# Acoustics_Preamp.net
KiCad netlist of a schematic drawn in Altium Designer
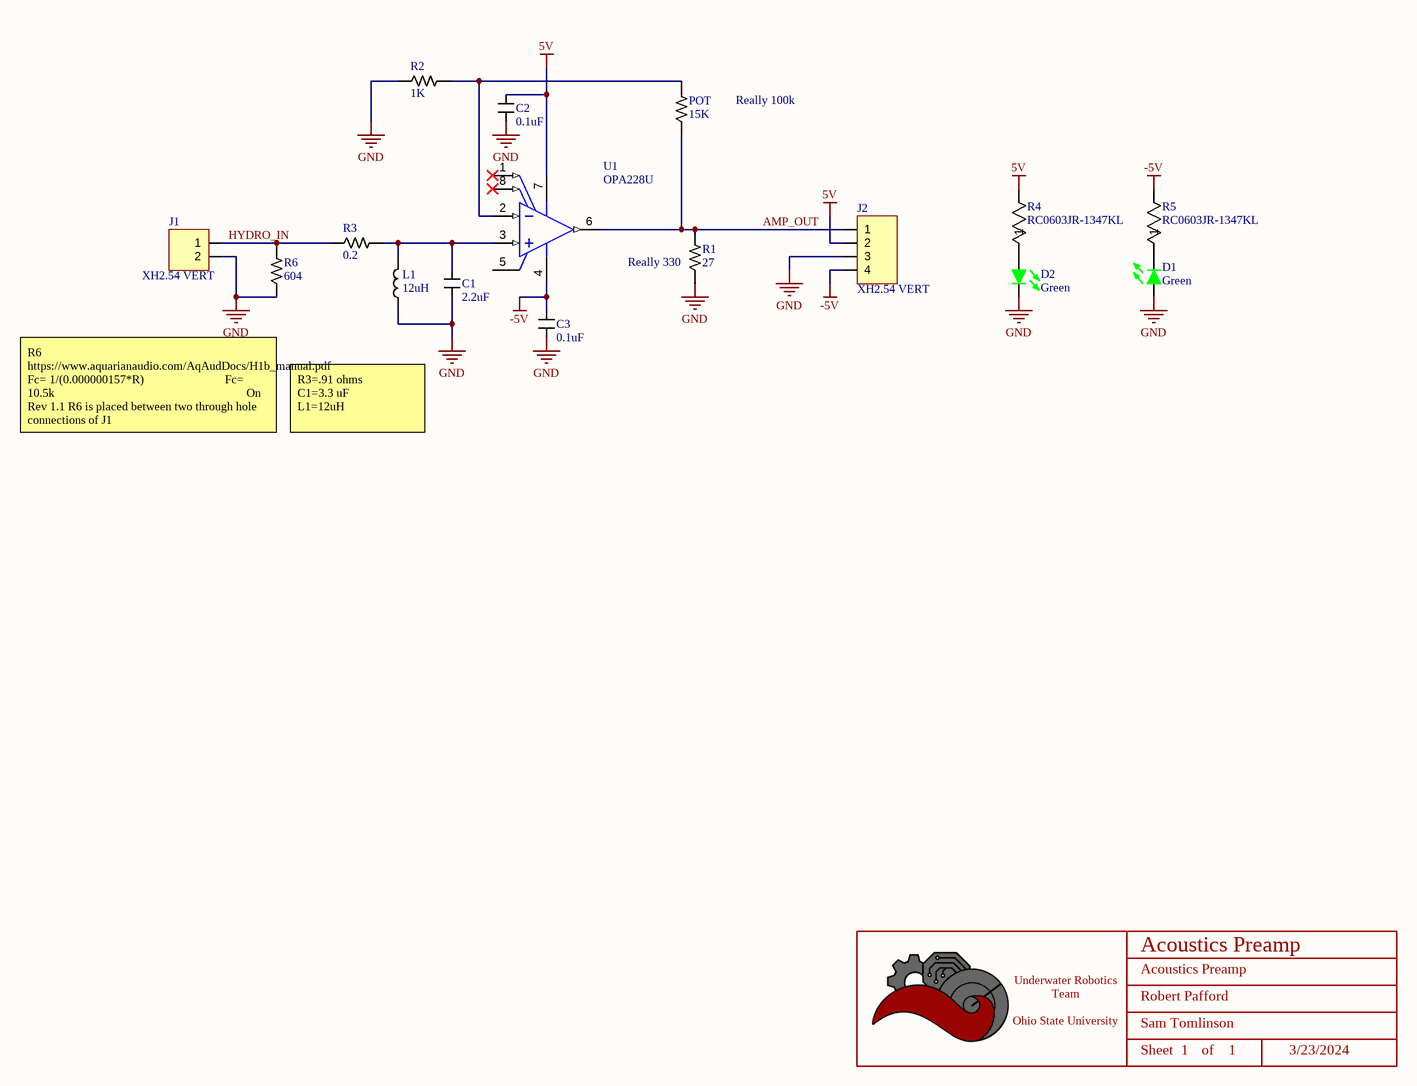
[diagram p0: Acoustics_Preamp.SchDoc]

(export (version "E")
  (design (tool "Eeschema 10.0.6"))
  (components
    (comp (ref "*")
      (value "Title_Block")
      (footprint "LOGO")
      (description "UWRT Schematic Title Block Template\r\n\r\nCreated June 2021, Dylan Trainor")
      (libsource (lib "UWRT") (part "Title_Block"))
    )
    (comp (ref "C1")
      (value "2.2uF")
      (footprint "CAPACITOR_0603")
      (description "CAP CER 2.2PF 50V C0G/NP0 0603")
      (fields
        (field (name "TOLERANCE") "+/- 20%")
        (field (name "VOLTAGE") "6.3V")
        (field (name "MADE BY") "Flip B")
      )
      (libsource (lib "Capacitors") (part "CAPACITOR_22uF_0603"))
    )
    (comp (ref "C2")
      (value "0.1uF")
      (footprint "CAPACITOR_0603")
      (description "Cap 100nF 25V +/-10%\r\nCeramic 0603")
      (fields
        (field (name "TOLERANCE") "+/- 10%")
        (field (name "VOLTAGE") "6.3V")
        (field (name "MADE BY") "Flip B")
      )
      (libsource (lib "Capacitors") (part "CAPACITOR_0.1uF_0603_25V"))
    )
    (comp (ref "C3")
      (value "0.1uF")
      (footprint "CAPACITOR_0603")
      (description "Cap 100nF 25V +/-10%\r\nCeramic 0603")
      (fields
        (field (name "TOLERANCE") "+/- 10%")
        (field (name "VOLTAGE") "6.3V")
        (field (name "MADE BY") "Flip B")
      )
      (libsource (lib "Capacitors") (part "CAPACITOR_0.1uF_0603_25V"))
    )
    (comp (ref "D1")
      (value "150060GS75000")
      (footprint "LED_0603")
      (description "LED Green Vf= 3.2V If = 0.025A\r\n150060GS75000")
      (fields (field (name "COLOR") "Green") (field (name "MADE BY") "Flip B"))
      (libsource (lib "Diodes") (part "LED_Green_0603_3.2V"))
    )
    (comp (ref "D2")
      (value "150060GS75000")
      (footprint "LED_0603")
      (description "LED Green Vf= 3.2V If = 0.025A\r\n150060GS75000")
      (fields (field (name "COLOR") "Green") (field (name "MADE BY") "Flip B"))
      (libsource (lib "Diodes") (part "LED_Green_0603_3.2V"))
    )
    (comp (ref "J1")
      (value "XH2.54 VERT")
      (footprint "CONN_JST_XH254_2POS_VERT")
      (description "JST XH 2.54mm Pitch 2 Pos Vertical")
      (fields (field (name "MANUFACTURER") "JST") (field (name "CREATED BY") "Robert P"))
      (libsource (lib "Connectors") (part "CONN_JST_XH254_2POS_VERT"))
    )
    (comp (ref "J2")
      (value "XH2.54 VERT")
      (footprint "CONN_JST_XH254_4POS_VERT")
      (description "JST XH 2.54mm Pitch 4 Pos Vertical")
      (fields (field (name "MANUFACTURER") "JST") (field (name "CREATED BY") "Robert P"))
      (libsource (lib "Connectors") (part "CONN_JST_XH254_4POS_VERT"))
    )
    (comp (ref "L1")
      (value "12uH")
      (footprint "INDUCTOR_0603")
      (description "12 µH Shielded Multilayer Inductor 10 mA 1.8Ohm Max 0603 (1608 Metric)")
      (fields
        (field (name "TOLERANCE") "+/- 20%")
        (field (name "Comment") "FIXED IND 12UH 10MA 1.8 OHM SMD")
        (field (name "MADE BY") "Robert Pafford")
      )
      (libsource (lib "Inductors") (part "INDUCTOR_12uH_0603"))
    )
    (comp (ref "POT")
      (value "15k Ohm 5% 1/10W")
      (footprint "RESISTOR_0603")
      (description "RES 15k OHM 5% 1/10W 0603")
      (fields
        (field (name "TOLERANCE") "+/- 5%")
        (field (name "VALUE  (OHMS)") "15K")
        (field (name "MADE BY") "Dylan Trainor")
      )
      (libsource (lib "Resistors") (part "RESISTOR_15K_0603"))
    )
    (comp (ref "R1")
      (value "27 Ohm 5% 1/8W")
      (footprint "RESISTOR_0603")
      (description "RES 27 OHM 5% 1/8W 0603")
      (fields
        (field (name "TOLERANCE") "+/- 5%")
        (field (name "VALUE  (OHMS)") "27")
        (field (name "MADE BY") "Robert Pafford")
      )
      (libsource (lib "Resistors") (part "RESISTOR_27_0603"))
    )
    (comp (ref "R2")
      (value "1k Ohm 5% 1/8W")
      (footprint "RESISTOR_0603")
      (description "RES 1.8 OHM 5% 1/8W 0603")
      (fields
        (field (name "TOLERANCE") "+/- 5%")
        (field (name "VALUE  (OHMS)") "1K")
        (field (name "MADE BY") "Robert Pafford")
      )
      (libsource (lib "Resistors") (part "RESISTOR_1K_0603"))
    )
    (comp (ref "R3")
      (value "0.2 Ohm 5% 1/8W")
      (footprint "RESISTOR_0603")
      (description "RES 0.2 OHM 5% 1/8W 0603")
      (fields
        (field (name "TOLERANCE") "+/- 5%")
        (field (name "VALUE  (OHMS)") "0.2")
        (field (name "MADE BY") "Robert Pafford")
      )
      (libsource (lib "Resistors") (part "RESISTOR_0.2_0603"))
    )
    (comp (ref "R4")
      (value "RC0603JR-1347KL")
      (footprint "RESISTOR_0603")
      (description "47kohm 0603 1/10w")
      (fields (field (name "COPYRIGHT") "Copyright (C) 2024 Ultra Librarian. All rights reserved."))
      (libsource (lib "Resistors") (part "RC0603JR-1347KL"))
    )
    (comp (ref "R5")
      (value "RC0603JR-1347KL")
      (footprint "RESISTOR_0603")
      (description "47kohm 0603 1/10w")
      (fields (field (name "COPYRIGHT") "Copyright (C) 2024 Ultra Librarian. All rights reserved."))
      (libsource (lib "Resistors") (part "RC0603JR-1347KL"))
    )
    (comp (ref "R6")
      (value "604 Ohm 1% 1/16W")
      (footprint "RESISTOR_0402")
      (description "RES 604 OHM 1% 1/16W 0402")
      (fields
        (field (name "TOLERANCE") "+/- 1%")
        (field (name "VALUE  (OHMS)") "604")
        (field (name "MADE BY") "Robert Pafford")
      )
      (libsource (lib "Resistors") (part "RESISTOR_604_0402"))
    )
    (comp (ref "U1")
      (value "OPA228U")
      (footprint "D0008A_M")
      (fields (field (name "MANUFACTURER") "Texas Instruments"))
      (libsource (lib "Altium Content Vault") (part "TI-OPA228-X8"))
    )
  )
  (nets
    (net (code "1") (name "-5V") (class "Default")
      (node (ref "C3") (pin "1") (pinfunction "1_1") (pintype "passive"))
      (node (ref "J2") (pin "4") (pinfunction "4_4") (pintype "passive"))
      (node (ref "R5") (pin "2") (pinfunction "2_2") (pintype "passive"))
      (node (ref "U1") (pin "4") (pinfunction "V-_4") (pintype "power_in"))
    )
    (net (code "3") (name "/AMP_OUT") (class "Default")
      (node (ref "J2") (pin "1") (pinfunction "1_1") (pintype "passive"))
      (node (ref "POT") (pin "2") (pinfunction "2_2") (pintype "passive"))
      (node (ref "R1") (pin "1") (pinfunction "1_1") (pintype "passive"))
      (node (ref "U1") (pin "6") (pinfunction "OUT_6") (pintype "output"))
    )
    (net (code "4") (name "/HYDRO_IN") (class "Default")
      (node (ref "J1") (pin "1") (pinfunction "1_1") (pintype "passive"))
      (node (ref "R3") (pin "2") (pinfunction "2_2") (pintype "passive"))
      (node (ref "R6") (pin "1") (pinfunction "1_1") (pintype "passive"))
    )
    (net (code "5") (name "5V") (class "Default")
      (node (ref "C2") (pin "1") (pinfunction "1_1") (pintype "passive"))
      (node (ref "J2") (pin "2") (pinfunction "2_2") (pintype "passive"))
      (node (ref "R4") (pin "2") (pinfunction "2_2") (pintype "passive"))
      (node (ref "U1") (pin "7") (pinfunction "V+_7") (pintype "power_in"))
    )
    (net (code "6") (name "GND") (class "Default")
      (node (ref "C1") (pin "2") (pinfunction "2_2") (pintype "passive"))
      (node (ref "C2") (pin "2") (pinfunction "2_2") (pintype "passive"))
      (node (ref "C3") (pin "2") (pinfunction "2_2") (pintype "passive"))
      (node (ref "D1") (pin "1") (pinfunction "1_1") (pintype "passive"))
      (node (ref "D2") (pin "2") (pinfunction "2_2") (pintype "passive"))
      (node (ref "J1") (pin "2") (pinfunction "2_2") (pintype "passive"))
      (node (ref "J2") (pin "3") (pinfunction "3_3") (pintype "passive"))
      (node (ref "L1") (pin "2") (pinfunction "2_2") (pintype "passive"))
      (node (ref "R1") (pin "2") (pinfunction "2_2") (pintype "passive"))
      (node (ref "R2") (pin "2") (pinfunction "2_2") (pintype "passive"))
      (node (ref "R6") (pin "2") (pinfunction "2_2") (pintype "passive"))
    )
    (net (code "7") (name "Net-(D1-Pad2)") (class "Default")
      (node (ref "D1") (pin "2") (pinfunction "2_2") (pintype "passive"))
      (node (ref "R5") (pin "1") (pinfunction "1_1") (pintype "passive"))
    )
    (net (code "8") (name "Net-(D2-Pad1)") (class "Default")
      (node (ref "D2") (pin "1") (pinfunction "1_1") (pintype "passive"))
      (node (ref "R4") (pin "1") (pinfunction "1_1") (pintype "passive"))
    )
    (net (code "9") (name "Net-(U1-IN+)") (class "Default")
      (node (ref "C1") (pin "1") (pinfunction "1_1") (pintype "passive"))
      (node (ref "L1") (pin "1") (pinfunction "1_1") (pintype "passive"))
      (node (ref "R3") (pin "1") (pinfunction "1_1") (pintype "passive"))
      (node (ref "U1") (pin "3") (pinfunction "IN+_3") (pintype "input"))
    )
    (net (code "10") (name "Net-(U1-IN-)") (class "Default")
      (node (ref "POT") (pin "1") (pinfunction "1_1") (pintype "passive"))
      (node (ref "R2") (pin "1") (pinfunction "1_1") (pintype "passive"))
      (node (ref "U1") (pin "2") (pinfunction "IN-_2") (pintype "input"))
    )
    (net (code "11") (name "unconnected-(U1-NC-Pad5)") (class "Default")
      (node (ref "U1") (pin "5") (pinfunction "NC_5") (pintype "passive"))
    )
    (net (code "12") (name "unconnected-(U1-TRIM-Pad1)") (class "Default")
      (node (ref "U1") (pin "1") (pinfunction "TRIM_1") (pintype "input+no_connect"))
    )
    (net (code "13") (name "unconnected-(U1-TRIM-Pad8)") (class "Default")
      (node (ref "U1") (pin "8") (pinfunction "TRIM_8") (pintype "input+no_connect"))
    )
  )
)
